# triangle2sine.net
KiCad netlist of a schematic drawn in Altium Designer
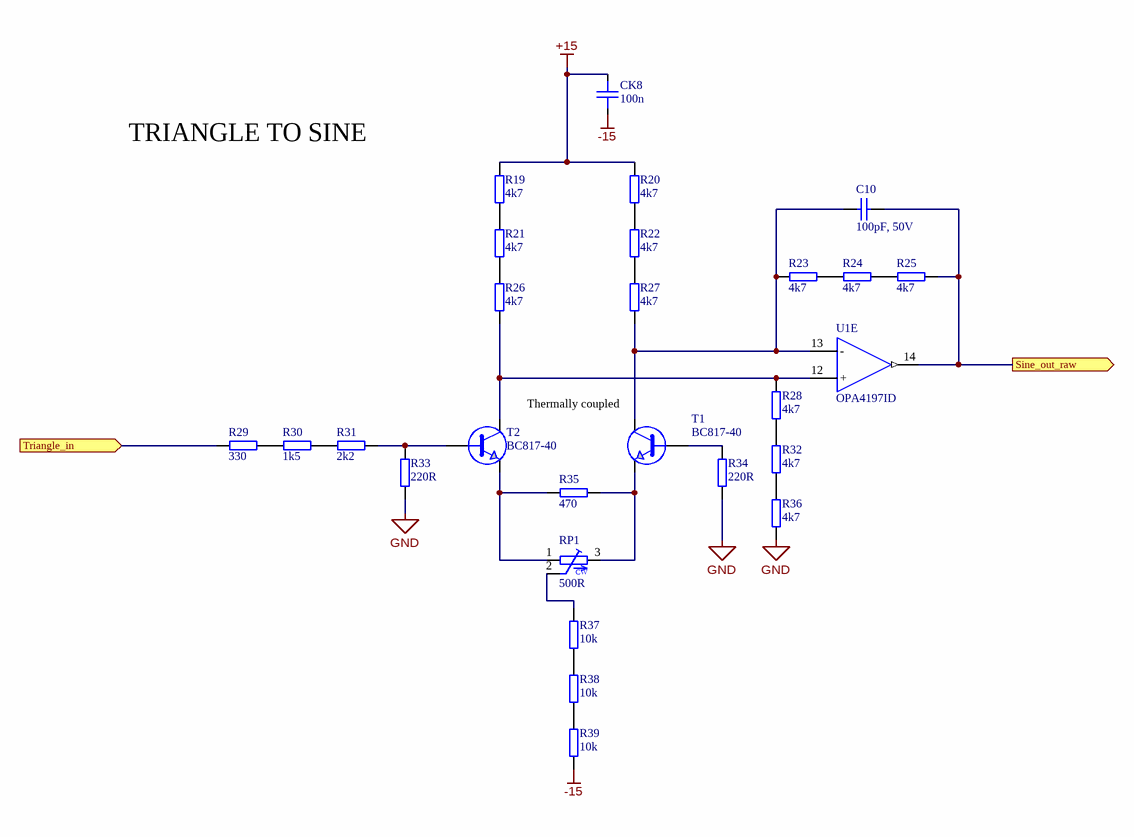
[diagram p0: triangle2sine.SchDoc]

(export (version "E")
  (design (tool "Eeschema 10.0.6"))
  (components
    (comp (ref "C10")
      (value "100pF, 50V")
      (footprint "WCAP-CSGP_0805_L2W1.25H0.6_Reflow")
      (description "WCAP-CSGP Multilayer Ceramic Chip Capacitor, General Purpose, size 0805, NP0, 100pF, 50V")
      (fields
        (field (name "MANUFACTURER") "Wurth Elektronik")
        (field (name "MANUFACTURER PART NUMBER") "885012007057")
      )
      (libsource (lib "Altium_WCAP-CSGP (rev22a)") (part "885012007057"))
    )
    (comp (ref "CK8")
      (value "100n")
      (footprint "CAPC1608X09N(SMC0603)")
      (description "C; 100n; 50V; 10%; X7R; ??;")
      (libsource (lib "altium_sql") (part "CK"))
    )
    (comp (ref "R19")
      (value "4k7")
      (footprint "RESC1608X06N(SMR0603)")
      (description "Thick Film resistor, 0603 Size, universal value, 0.1 W")
      (libsource (lib "Kubikova integrovana knihovna ") (part "R 0603 universal"))
    )
    (comp (ref "R20")
      (value "4k7")
      (footprint "RESC1608X06N(SMR0603)")
      (description "Thick Film resistor, 0603 Size, universal value, 0.1 W")
      (libsource (lib "Kubikova integrovana knihovna ") (part "R 0603 universal"))
    )
    (comp (ref "R21")
      (value "4k7")
      (footprint "RESC1608X06N(SMR0603)")
      (description "Thick Film resistor, 0603 Size, universal value, 0.1 W")
      (libsource (lib "Kubikova integrovana knihovna ") (part "R 0603 universal"))
    )
    (comp (ref "R22")
      (value "4k7")
      (footprint "RESC1608X06N(SMR0603)")
      (description "Thick Film resistor, 0603 Size, universal value, 0.1 W")
      (libsource (lib "Kubikova integrovana knihovna ") (part "R 0603 universal"))
    )
    (comp (ref "R23")
      (value "4k7")
      (footprint "RESC1608X06N(SMR0603)")
      (description "Thick Film resistor, 0603 Size, universal value, 0.1 W")
      (libsource (lib "Kubikova integrovana knihovna ") (part "R 0603 universal"))
    )
    (comp (ref "R24")
      (value "4k7")
      (footprint "RESC1608X06N(SMR0603)")
      (description "Thick Film resistor, 0603 Size, universal value, 0.1 W")
      (libsource (lib "Kubikova integrovana knihovna ") (part "R 0603 universal"))
    )
    (comp (ref "R25")
      (value "4k7")
      (footprint "RESC1608X06N(SMR0603)")
      (description "Thick Film resistor, 0603 Size, universal value, 0.1 W")
      (libsource (lib "Kubikova integrovana knihovna ") (part "R 0603 universal"))
    )
    (comp (ref "R26")
      (value "4k7")
      (footprint "RESC1608X06N(SMR0603)")
      (description "Thick Film resistor, 0603 Size, universal value, 0.1 W")
      (libsource (lib "Kubikova integrovana knihovna ") (part "R 0603 universal"))
    )
    (comp (ref "R27")
      (value "4k7")
      (footprint "RESC1608X06N(SMR0603)")
      (description "Thick Film resistor, 0603 Size, universal value, 0.1 W")
      (libsource (lib "Kubikova integrovana knihovna ") (part "R 0603 universal"))
    )
    (comp (ref "R28")
      (value "4k7")
      (footprint "RESC1608X06N(SMR0603)")
      (description "Thick Film resistor, 0603 Size, universal value, 0.1 W")
      (libsource (lib "Kubikova integrovana knihovna ") (part "R 0603 universal"))
    )
    (comp (ref "R29")
      (value "330")
      (footprint "RESC1608X06N(SMR0603)")
      (description "Thick Film resistor, 0603 Size, universal value, 0.1 W")
      (libsource (lib "Kubikova integrovana knihovna ") (part "R 0603 universal"))
    )
    (comp (ref "R30")
      (value "1k5")
      (footprint "RESC1608X06N(SMR0603)")
      (description "Thick Film resistor, 0603 Size, universal value, 0.1 W")
      (libsource (lib "Kubikova integrovana knihovna ") (part "R 0603 universal"))
    )
    (comp (ref "R31")
      (value "2k2")
      (footprint "RESC1608X06N(SMR0603)")
      (description "Thick Film resistor, 0603 Size, universal value, 0.1 W")
      (libsource (lib "Kubikova integrovana knihovna ") (part "R 0603 universal"))
    )
    (comp (ref "R32")
      (value "4k7")
      (footprint "RESC1608X06N(SMR0603)")
      (description "Thick Film resistor, 0603 Size, universal value, 0.1 W")
      (libsource (lib "Kubikova integrovana knihovna ") (part "R 0603 universal"))
    )
    (comp (ref "R33")
      (value "220R")
      (footprint "RESC1608X06N(SMR0603)")
      (description "Thick Film resistor, 0603 Size, universal value, 0.1 W")
      (libsource (lib "Kubikova integrovana knihovna ") (part "R 0603 universal"))
    )
    (comp (ref "R34")
      (value "220R")
      (footprint "RESC1608X06N(SMR0603)")
      (description "Thick Film resistor, 0603 Size, universal value, 0.1 W")
      (libsource (lib "Kubikova integrovana knihovna ") (part "R 0603 universal"))
    )
    (comp (ref "R35")
      (value "470")
      (footprint "RESC1608X06N(SMR0603)")
      (description "Thick Film resistor, 0603 Size, universal value, 0.1 W")
      (libsource (lib "Kubikova integrovana knihovna ") (part "R 0603 universal"))
    )
    (comp (ref "R36")
      (value "4k7")
      (footprint "RESC1608X06N(SMR0603)")
      (description "Thick Film resistor, 0603 Size, universal value, 0.1 W")
      (libsource (lib "Kubikova integrovana knihovna ") (part "R 0603 universal"))
    )
    (comp (ref "R37")
      (value "10k")
      (footprint "RESC1608X06N(SMR0603)")
      (description "Thick Film resistor, 0603 Size, universal value, 0.1 W")
      (libsource (lib "Kubikova integrovana knihovna ") (part "R 0603 universal"))
    )
    (comp (ref "R38")
      (value "10k")
      (footprint "RESC1608X06N(SMR0603)")
      (description "Thick Film resistor, 0603 Size, universal value, 0.1 W")
      (libsource (lib "Kubikova integrovana knihovna ") (part "R 0603 universal"))
    )
    (comp (ref "R39")
      (value "10k")
      (footprint "RESC1608X06N(SMR0603)")
      (description "Thick Film resistor, 0603 Size, universal value, 0.1 W")
      (libsource (lib "Kubikova integrovana knihovna ") (part "R 0603 universal"))
    )
    (comp (ref "RP1")
      (value "500R")
      (footprint "64W")
      (description "R; 500R; 0.5W; 10%; 250V; Variable; ±100ppm/K; 1x;")
      (fields (field (name "MANUFACTURER") "VISHAY: T93YA501KT20"))
      (libsource (lib "altium_sql") (part "RP"))
    )
    (comp (ref "T1")
      (value "BC817-40")
      (footprint "SOT95P230X110-3N(SOT23)")
      (description "SSw; NPN; ??Ohm; 45V; 0.5A; 1x;")
      (libsource (lib "altium_sql") (part "NPN_BEC"))
    )
    (comp (ref "T2")
      (value "BC817-40")
      (footprint "SOT95P230X110-3N(SOT23)")
      (description "SSw; NPN; ??Ohm; 45V; 0.5A; 1x;")
      (libsource (lib "altium_sql") (part "NPN_BEC"))
    )
    (comp (ref "U1")
      (value "OPA4197ID")
      (footprint "SOIC127P600X175-14N(SO-14)")
      (description "IC; Opamp; 4.5V; 36V; 4x;")
      (libsource (lib "altium_sql") (part "OP_AMP_QUAD_1"))
    )
  )
  (nets
    (net (code "1") (name "+15") (class "Default")
      (node (ref "CK8") (pin "1") (pinfunction "1_1") (pintype "passive"))
      (node (ref "R19") (pin "2") (pinfunction "2_2") (pintype "passive"))
      (node (ref "R20") (pin "2") (pinfunction "2_2") (pintype "passive"))
    )
    (net (code "2") (name "-15") (class "Default")
      (node (ref "CK8") (pin "2") (pinfunction "2_2") (pintype "passive"))
      (node (ref "R39") (pin "1") (pinfunction "1_1") (pintype "passive"))
    )
    (net (code "3") (name "/Sine_out_raw") (class "Default")
      (node (ref "C10") (pin "2") (pinfunction "2_2") (pintype "passive"))
      (node (ref "R25") (pin "1") (pinfunction "1_1") (pintype "passive"))
      (node (ref "U1") (pin "14") (pinfunction "OUT4_14") (pintype "output"))
    )
    (net (code "4") (name "/Triangle_in") (class "Default")
      (node (ref "R29") (pin "1") (pinfunction "1_1") (pintype "passive"))
    )
    (net (code "5") (name "GND") (class "Default")
      (node (ref "R33") (pin "1") (pinfunction "1_1") (pintype "passive"))
      (node (ref "R34") (pin "1") (pinfunction "1_1") (pintype "passive"))
      (node (ref "R36") (pin "2") (pinfunction "2_2") (pintype "passive"))
    )
    (net (code "6") (name "Net-(R19-Pad1)") (class "Default")
      (node (ref "R19") (pin "1") (pinfunction "1_1") (pintype "passive"))
      (node (ref "R21") (pin "2") (pinfunction "2_2") (pintype "passive"))
    )
    (net (code "7") (name "Net-(R20-Pad1)") (class "Default")
      (node (ref "R20") (pin "1") (pinfunction "1_1") (pintype "passive"))
      (node (ref "R22") (pin "2") (pinfunction "2_2") (pintype "passive"))
    )
    (net (code "8") (name "Net-(R21-Pad1)") (class "Default")
      (node (ref "R21") (pin "1") (pinfunction "1_1") (pintype "passive"))
      (node (ref "R26") (pin "2") (pinfunction "2_2") (pintype "passive"))
    )
    (net (code "9") (name "Net-(R22-Pad1)") (class "Default")
      (node (ref "R22") (pin "1") (pinfunction "1_1") (pintype "passive"))
      (node (ref "R27") (pin "2") (pinfunction "2_2") (pintype "passive"))
    )
    (net (code "10") (name "Net-(R23-Pad1)") (class "Default")
      (node (ref "R23") (pin "1") (pinfunction "1_1") (pintype "passive"))
      (node (ref "R24") (pin "2") (pinfunction "2_2") (pintype "passive"))
    )
    (net (code "11") (name "Net-(R24-Pad1)") (class "Default")
      (node (ref "R24") (pin "1") (pinfunction "1_1") (pintype "passive"))
      (node (ref "R25") (pin "2") (pinfunction "2_2") (pintype "passive"))
    )
    (net (code "12") (name "Net-(R28-Pad2)") (class "Default")
      (node (ref "R28") (pin "2") (pinfunction "2_2") (pintype "passive"))
      (node (ref "R32") (pin "1") (pinfunction "1_1") (pintype "passive"))
    )
    (net (code "13") (name "Net-(R29-Pad2)") (class "Default")
      (node (ref "R29") (pin "2") (pinfunction "2_2") (pintype "passive"))
      (node (ref "R30") (pin "1") (pinfunction "1_1") (pintype "passive"))
    )
    (net (code "14") (name "Net-(R30-Pad2)") (class "Default")
      (node (ref "R30") (pin "2") (pinfunction "2_2") (pintype "passive"))
      (node (ref "R31") (pin "1") (pinfunction "1_1") (pintype "passive"))
    )
    (net (code "15") (name "Net-(R32-Pad2)") (class "Default")
      (node (ref "R32") (pin "2") (pinfunction "2_2") (pintype "passive"))
      (node (ref "R36") (pin "1") (pinfunction "1_1") (pintype "passive"))
    )
    (net (code "16") (name "Net-(R37-Pad1)") (class "Default")
      (node (ref "R37") (pin "1") (pinfunction "1_1") (pintype "passive"))
      (node (ref "R38") (pin "2") (pinfunction "2_2") (pintype "passive"))
    )
    (net (code "17") (name "Net-(R37-Pad2)") (class "Default")
      (node (ref "R37") (pin "2") (pinfunction "2_2") (pintype "passive"))
      (node (ref "RP1") (pin "2") (pinfunction "2_2") (pintype "passive"))
    )
    (net (code "18") (name "Net-(R38-Pad1)") (class "Default")
      (node (ref "R38") (pin "1") (pinfunction "1_1") (pintype "passive"))
      (node (ref "R39") (pin "2") (pinfunction "2_2") (pintype "passive"))
    )
    (net (code "19") (name "Net-(T1-B)") (class "Default")
      (node (ref "R34") (pin "2") (pinfunction "2_2") (pintype "passive"))
      (node (ref "T1") (pin "1") (pinfunction "B_1") (pintype "passive"))
    )
    (net (code "20") (name "Net-(T1-C)") (class "Default")
      (node (ref "C10") (pin "1") (pinfunction "1_1") (pintype "passive"))
      (node (ref "R23") (pin "2") (pinfunction "2_2") (pintype "passive"))
      (node (ref "R27") (pin "1") (pinfunction "1_1") (pintype "passive"))
      (node (ref "T1") (pin "3") (pinfunction "C_3") (pintype "passive"))
      (node (ref "U1") (pin "13") (pinfunction "-_13") (pintype "passive"))
    )
    (net (code "21") (name "Net-(T1-E)") (class "Default")
      (node (ref "R35") (pin "1") (pinfunction "1_1") (pintype "passive"))
      (node (ref "RP1") (pin "3") (pinfunction "3_3") (pintype "passive"))
      (node (ref "T1") (pin "2") (pinfunction "E_2") (pintype "passive"))
    )
    (net (code "22") (name "Net-(T2-B)") (class "Default")
      (node (ref "R31") (pin "2") (pinfunction "2_2") (pintype "passive"))
      (node (ref "R33") (pin "2") (pinfunction "2_2") (pintype "passive"))
      (node (ref "T2") (pin "1") (pinfunction "B_1") (pintype "passive"))
    )
    (net (code "23") (name "Net-(T2-C)") (class "Default")
      (node (ref "R26") (pin "1") (pinfunction "1_1") (pintype "passive"))
      (node (ref "R28") (pin "1") (pinfunction "1_1") (pintype "passive"))
      (node (ref "T2") (pin "3") (pinfunction "C_3") (pintype "passive"))
      (node (ref "U1") (pin "12") (pinfunction "+_12") (pintype "passive"))
    )
    (net (code "24") (name "Net-(T2-E)") (class "Default")
      (node (ref "R35") (pin "2") (pinfunction "2_2") (pintype "passive"))
      (node (ref "RP1") (pin "1") (pinfunction "1_1") (pintype "passive"))
      (node (ref "T2") (pin "2") (pinfunction "E_2") (pintype "passive"))
    )
  )
)
